# ecg_2017_nano.net
KiCad netlist of a schematic drawn in EAGLE
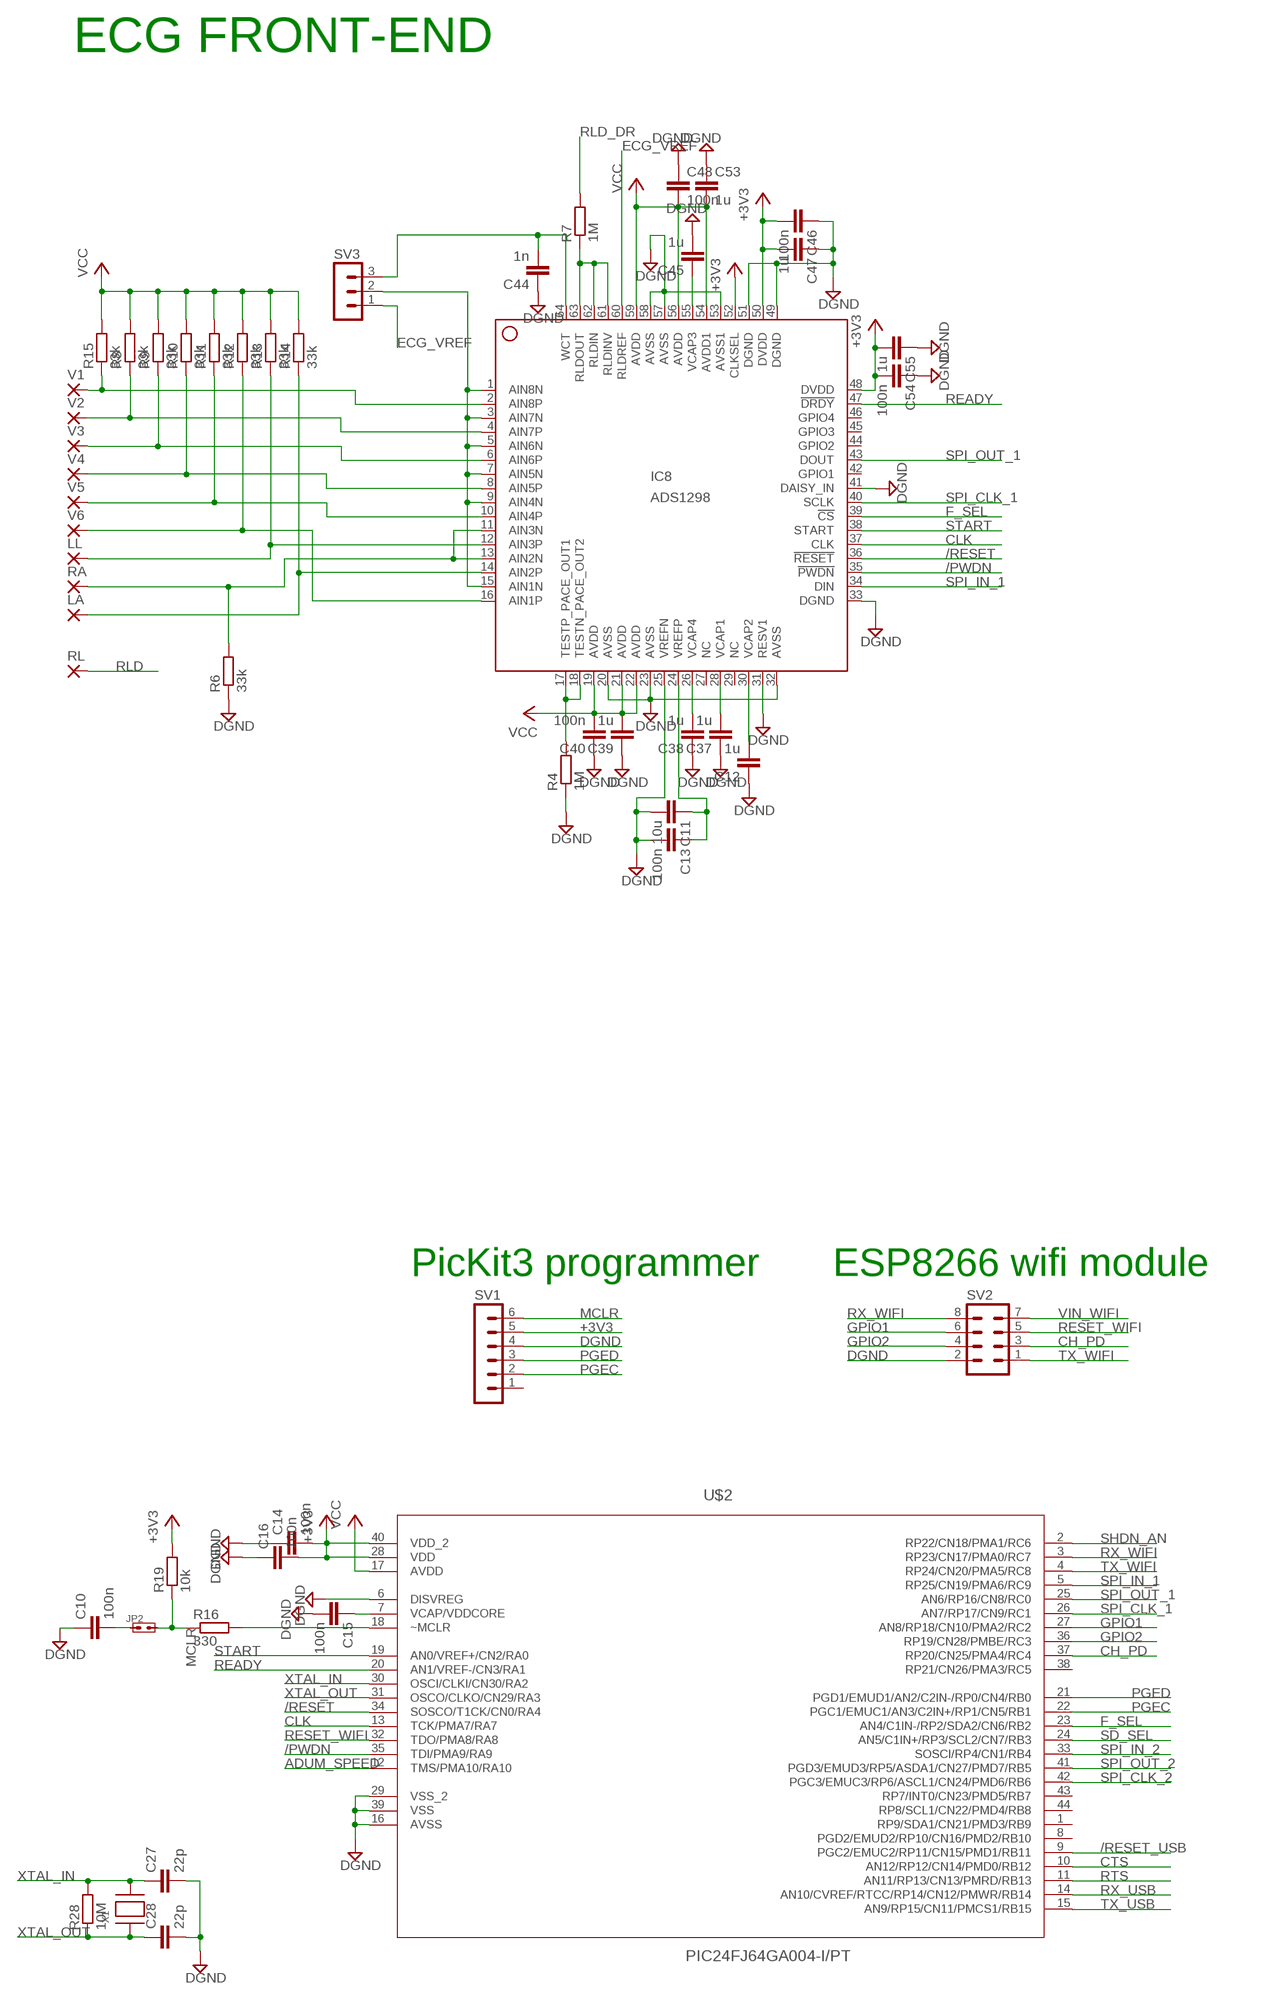
[diagram p0: schematic, sheet 1, part 1 of 2]
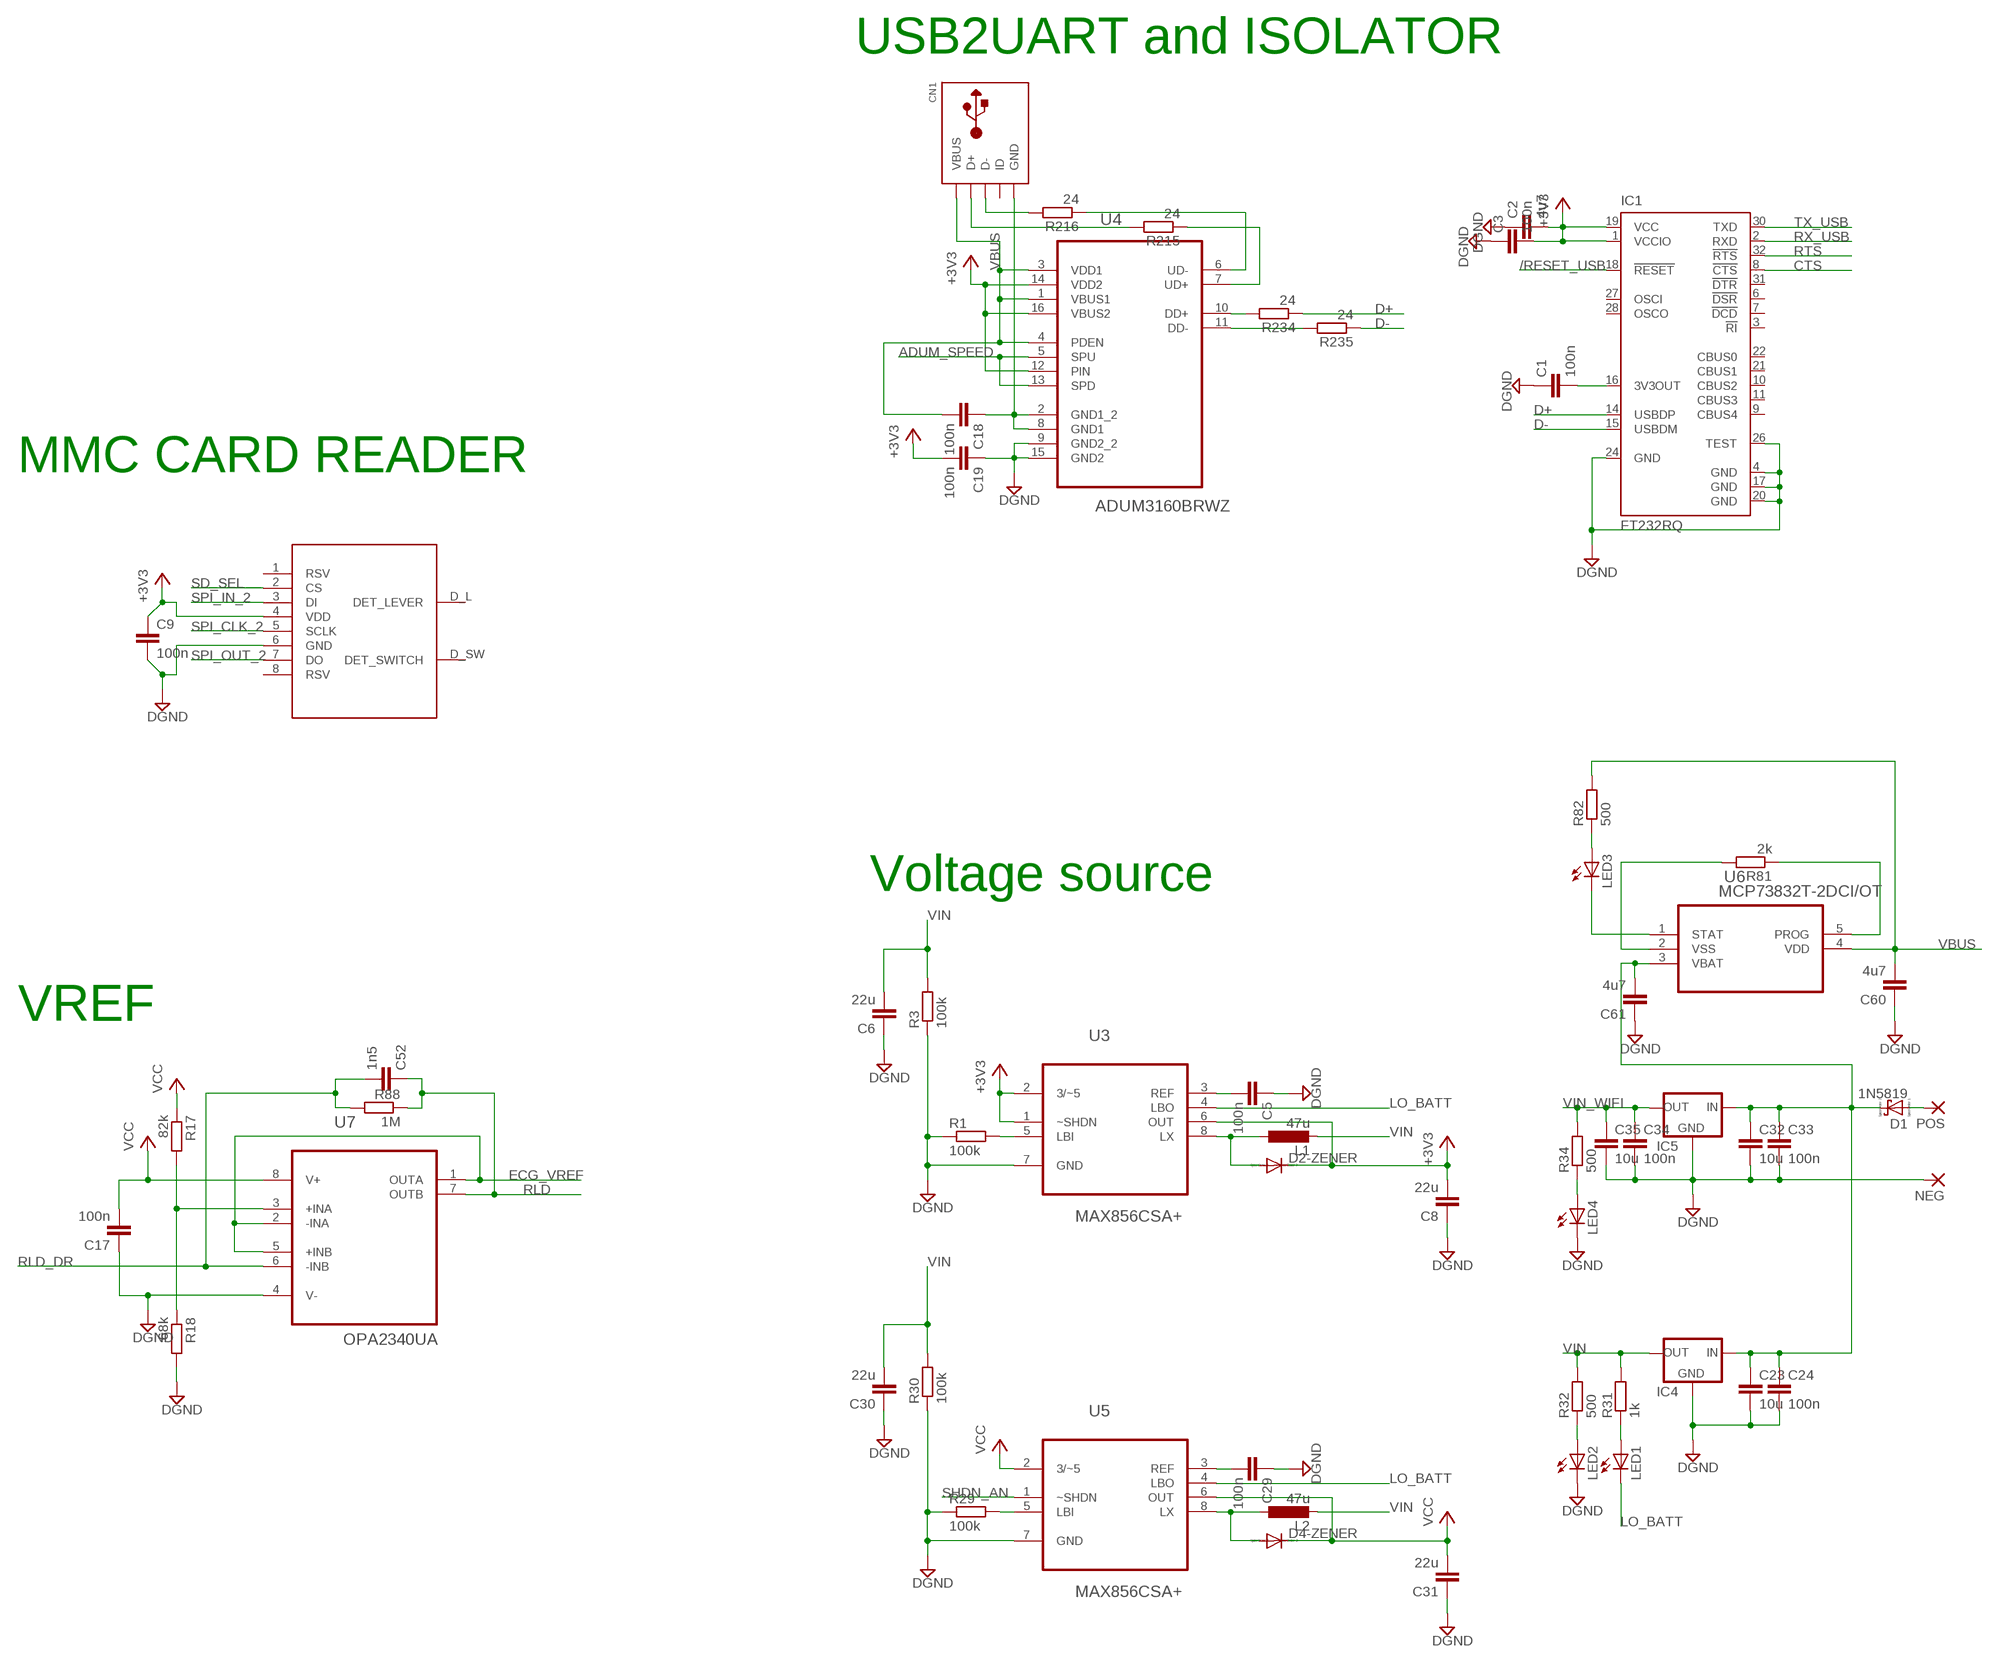
[diagram p1: schematic, sheet 1, part 2 of 2]

(export (version "E")
  (design (tool "Eeschema 10.0.6"))
  (components
    (comp (ref "C1")
      (value "100n")
      (footprint "eagle-import:C0603")
      (libsource (lib "eagle-import") (part "C-EUC0603"))
    )
    (comp (ref "C2")
      (value "4u7")
      (footprint "eagle-import:C0603")
      (libsource (lib "eagle-import") (part "C-EUC0603"))
    )
    (comp (ref "C3")
      (value "100n")
      (footprint "eagle-import:C0603")
      (libsource (lib "eagle-import") (part "C-EUC0603"))
    )
    (comp (ref "C5")
      (value "100n")
      (footprint "eagle-import:C0805")
      (libsource (lib "eagle-import") (part "C-EUC0805"))
    )
    (comp (ref "C6")
      (value "22u")
      (footprint "eagle-import:C0805")
      (libsource (lib "eagle-import") (part "C-EUC0805"))
    )
    (comp (ref "C8")
      (value "22u")
      (footprint "eagle-import:C0805")
      (libsource (lib "eagle-import") (part "C-EUC0805"))
    )
    (comp (ref "C9")
      (value "100n")
      (footprint "eagle-import:C0603")
      (libsource (lib "eagle-import") (part "C-EUC0603"))
    )
    (comp (ref "C10")
      (value "100n")
      (footprint "eagle-import:C0603")
      (libsource (lib "eagle-import") (part "C-EUC0603"))
    )
    (comp (ref "C11")
      (value "10u")
      (footprint "eagle-import:C0402")
      (libsource (lib "eagle-import") (part "C-EUC0402"))
    )
    (comp (ref "C12")
      (value "1u")
      (footprint "eagle-import:C0402")
      (libsource (lib "eagle-import") (part "C-EUC0402"))
    )
    (comp (ref "C13")
      (value "100n")
      (footprint "eagle-import:C0402")
      (libsource (lib "eagle-import") (part "C-EUC0402"))
    )
    (comp (ref "C14")
      (value "100n")
      (footprint "eagle-import:C0603")
      (libsource (lib "eagle-import") (part "C-EUC0603"))
    )
    (comp (ref "C15")
      (value "100n")
      (footprint "eagle-import:C0603")
      (libsource (lib "eagle-import") (part "C-EUC0603"))
    )
    (comp (ref "C16")
      (value "100n")
      (footprint "eagle-import:C0603")
      (libsource (lib "eagle-import") (part "C-EUC0603"))
    )
    (comp (ref "C17")
      (value "100n")
      (footprint "eagle-import:C0603")
      (libsource (lib "eagle-import") (part "C-EUC0603"))
    )
    (comp (ref "C18")
      (value "100n")
      (footprint "eagle-import:C0603")
      (libsource (lib "eagle-import") (part "C-EUC0603"))
    )
    (comp (ref "C19")
      (value "100n")
      (footprint "eagle-import:C0603")
      (libsource (lib "eagle-import") (part "C-EUC0603"))
    )
    (comp (ref "C23")
      (value "10u")
      (footprint "eagle-import:C0805")
      (libsource (lib "eagle-import") (part "C-EUC0805"))
    )
    (comp (ref "C24")
      (value "100n")
      (footprint "eagle-import:C0805")
      (libsource (lib "eagle-import") (part "C-EUC0805"))
    )
    (comp (ref "C27")
      (value "22p")
      (footprint "eagle-import:C0603")
      (libsource (lib "eagle-import") (part "C-EUC0603"))
    )
    (comp (ref "C28")
      (value "22p")
      (footprint "eagle-import:C0603")
      (libsource (lib "eagle-import") (part "C-EUC0603"))
    )
    (comp (ref "C29")
      (value "100n")
      (footprint "eagle-import:C0805")
      (libsource (lib "eagle-import") (part "C-EUC0805"))
    )
    (comp (ref "C30")
      (value "22u")
      (footprint "eagle-import:C0805")
      (libsource (lib "eagle-import") (part "C-EUC0805"))
    )
    (comp (ref "C31")
      (value "22u")
      (footprint "eagle-import:C0805")
      (libsource (lib "eagle-import") (part "C-EUC0805"))
    )
    (comp (ref "C32")
      (value "10u")
      (footprint "eagle-import:C0805")
      (libsource (lib "eagle-import") (part "C-EUC0805"))
    )
    (comp (ref "C33")
      (value "100n")
      (footprint "eagle-import:C0805")
      (libsource (lib "eagle-import") (part "C-EUC0805"))
    )
    (comp (ref "C34")
      (value "100n")
      (footprint "eagle-import:C0805")
      (libsource (lib "eagle-import") (part "C-EUC0805"))
    )
    (comp (ref "C35")
      (value "10u")
      (footprint "eagle-import:C0805")
      (libsource (lib "eagle-import") (part "C-EUC0805"))
    )
    (comp (ref "C37")
      (value "1u")
      (footprint "eagle-import:C0402")
      (libsource (lib "eagle-import") (part "C-EUC0402"))
    )
    (comp (ref "C38")
      (value "1u")
      (footprint "eagle-import:C0402")
      (libsource (lib "eagle-import") (part "C-EUC0402"))
    )
    (comp (ref "C39")
      (value "1u")
      (footprint "eagle-import:C0402")
      (libsource (lib "eagle-import") (part "C-EUC0402"))
    )
    (comp (ref "C40")
      (value "100n")
      (footprint "eagle-import:C0402")
      (libsource (lib "eagle-import") (part "C-EUC0402"))
    )
    (comp (ref "C44")
      (value "1n")
      (footprint "eagle-import:C0402")
      (libsource (lib "eagle-import") (part "C-EUC0402"))
    )
    (comp (ref "C45")
      (value "1u")
      (footprint "eagle-import:C0402")
      (libsource (lib "eagle-import") (part "C-EUC0402"))
    )
    (comp (ref "C46")
      (value "100n")
      (footprint "eagle-import:C0402")
      (libsource (lib "eagle-import") (part "C-EUC0402"))
    )
    (comp (ref "C47")
      (value "1u")
      (footprint "eagle-import:C0402")
      (libsource (lib "eagle-import") (part "C-EUC0402"))
    )
    (comp (ref "C48")
      (value "100n")
      (footprint "eagle-import:C0402")
      (libsource (lib "eagle-import") (part "C-EUC0402"))
    )
    (comp (ref "C52")
      (value "1n5")
      (footprint "eagle-import:C0603")
      (libsource (lib "eagle-import") (part "C-EUC0603"))
    )
    (comp (ref "C53")
      (value "1u")
      (footprint "eagle-import:C0402")
      (libsource (lib "eagle-import") (part "C-EUC0402"))
    )
    (comp (ref "C54")
      (value "100n")
      (footprint "eagle-import:C0402")
      (libsource (lib "eagle-import") (part "C-EUC0402"))
    )
    (comp (ref "C55")
      (value "1u")
      (footprint "eagle-import:C0402")
      (libsource (lib "eagle-import") (part "C-EUC0402"))
    )
    (comp (ref "C60")
      (value "4u7")
      (footprint "eagle-import:C0805")
      (libsource (lib "eagle-import") (part "C-EUC0805"))
    )
    (comp (ref "C61")
      (value "4u7")
      (footprint "eagle-import:C0805")
      (libsource (lib "eagle-import") (part "C-EUC0805"))
    )
    (comp (ref "CN1")
      (value "USBMINIB")
      (footprint "eagle-import:USB-MINIB")
      (libsource (lib "eagle-import") (part "USBMINIB"))
    )
    (comp (ref "D1")
      (value "1N5819")
      (footprint "eagle-import:DIODE_SMB")
      (libsource (lib "eagle-import") (part "SCHOTTKY-DIODE"))
    )
    (comp (ref "D2-ZENER")
      (value "DIODE-MICROMELF-R")
      (footprint "eagle-import:MICROMELF-R")
      (libsource (lib "eagle-import") (part "DIODE-MICROMELF-R"))
    )
    (comp (ref "D4-ZENER")
      (value "DIODE-MICROMELF-R")
      (footprint "eagle-import:MICROMELF-R")
      (libsource (lib "eagle-import") (part "DIODE-MICROMELF-R"))
    )
    (comp (ref "IC1")
      (value "FT232RQ")
      (footprint "eagle-import:QFN32")
      (libsource (lib "eagle-import") (part "FT232RQ"))
    )
    (comp (ref "IC4")
      (value "R-783.3-0.5")
      (footprint "eagle-import:R-78XX")
      (libsource (lib "eagle-import") (part "R-783.3-0.5"))
    )
    (comp (ref "IC5")
      (value "R-783.3-0.5")
      (footprint "eagle-import:R-78XX")
      (libsource (lib "eagle-import") (part "R-783.3-0.5"))
    )
    (comp (ref "IC8")
      (value "ADS1298")
      (footprint "eagle-import:HTQFP-64-PAP")
      (fields (field (name "MPN") "ADS1294IPAG"))
      (libsource (lib "eagle-import") (part "ADS1298"))
    )
    (comp (ref "JP2")
      (value "JMP2")
      (footprint "eagle-import:JP2")
      (libsource (lib "eagle-import") (part "JMP2"))
    )
    (comp (ref "L1")
      (value "47u")
      (footprint "eagle-import:L2012C")
      (libsource (lib "eagle-import") (part "L-EUL2012C"))
    )
    (comp (ref "L2")
      (value "47u")
      (footprint "eagle-import:L2012C")
      (libsource (lib "eagle-import") (part "L-EUL2012C"))
    )
    (comp (ref "LA")
      (value "2,54/1,0")
      (footprint "eagle-import:2,54_1,0")
      (libsource (lib "eagle-import") (part "2,54/1,0"))
    )
    (comp (ref "LED1")
      (value "LEDSML0805")
      (footprint "eagle-import:SML0805")
      (libsource (lib "eagle-import") (part "LEDSML0805"))
    )
    (comp (ref "LED2")
      (value "LEDSML0805")
      (footprint "eagle-import:SML0805")
      (libsource (lib "eagle-import") (part "LEDSML0805"))
    )
    (comp (ref "LED3")
      (value "LEDSML0805")
      (footprint "eagle-import:SML0805")
      (libsource (lib "eagle-import") (part "LEDSML0805"))
    )
    (comp (ref "LED4")
      (value "LEDSML0805")
      (footprint "eagle-import:SML0805")
      (libsource (lib "eagle-import") (part "LEDSML0805"))
    )
    (comp (ref "LL")
      (value "2,54/1,0")
      (footprint "eagle-import:2,54_1,0")
      (libsource (lib "eagle-import") (part "2,54/1,0"))
    )
    (comp (ref "NEG")
      (value "2,54/1,0")
      (footprint "eagle-import:2,54_1,0")
      (libsource (lib "eagle-import") (part "2,54/1,0"))
    )
    (comp (ref "POS")
      (value "2,54/1,0")
      (footprint "eagle-import:2,54_1,0")
      (libsource (lib "eagle-import") (part "2,54/1,0"))
    )
    (comp (ref "R1")
      (value "100k")
      (footprint "eagle-import:R0805")
      (libsource (lib "eagle-import") (part "R0805"))
    )
    (comp (ref "R3")
      (value "100k")
      (footprint "eagle-import:R0805")
      (libsource (lib "eagle-import") (part "R0805"))
    )
    (comp (ref "R4")
      (value "1M")
      (footprint "eagle-import:R0603")
      (libsource (lib "eagle-import") (part "R0603"))
    )
    (comp (ref "R6")
      (value "33k")
      (footprint "eagle-import:R0603")
      (libsource (lib "eagle-import") (part "R0603"))
    )
    (comp (ref "R7")
      (value "1M")
      (footprint "eagle-import:R0603")
      (libsource (lib "eagle-import") (part "R0603"))
    )
    (comp (ref "R8")
      (value "33k")
      (footprint "eagle-import:R0603")
      (libsource (lib "eagle-import") (part "R0603"))
    )
    (comp (ref "R9")
      (value "33k")
      (footprint "eagle-import:R0603")
      (libsource (lib "eagle-import") (part "R0603"))
    )
    (comp (ref "R10")
      (value "33k")
      (footprint "eagle-import:R0603")
      (libsource (lib "eagle-import") (part "R0603"))
    )
    (comp (ref "R11")
      (value "33k")
      (footprint "eagle-import:R0603")
      (libsource (lib "eagle-import") (part "R0603"))
    )
    (comp (ref "R12")
      (value "33k")
      (footprint "eagle-import:R0603")
      (libsource (lib "eagle-import") (part "R0603"))
    )
    (comp (ref "R13")
      (value "33k")
      (footprint "eagle-import:R0603")
      (libsource (lib "eagle-import") (part "R0603"))
    )
    (comp (ref "R14")
      (value "33k")
      (footprint "eagle-import:R0603")
      (libsource (lib "eagle-import") (part "R0603"))
    )
    (comp (ref "R15")
      (value "33k")
      (footprint "eagle-import:R0603")
      (libsource (lib "eagle-import") (part "R0603"))
    )
    (comp (ref "R16")
      (value "330")
      (footprint "eagle-import:R0603")
      (libsource (lib "eagle-import") (part "R0603"))
    )
    (comp (ref "R17")
      (value "82k")
      (footprint "eagle-import:R0603")
      (libsource (lib "eagle-import") (part "R0603"))
    )
    (comp (ref "R18")
      (value "68k")
      (footprint "eagle-import:R0603")
      (libsource (lib "eagle-import") (part "R0603"))
    )
    (comp (ref "R19")
      (value "10k")
      (footprint "eagle-import:R0603")
      (libsource (lib "eagle-import") (part "R0603"))
    )
    (comp (ref "R28")
      (value "10M")
      (footprint "eagle-import:R0603")
      (libsource (lib "eagle-import") (part "R-EU_R0603"))
    )
    (comp (ref "R29")
      (value "100k")
      (footprint "eagle-import:R0805")
      (libsource (lib "eagle-import") (part "R0805"))
    )
    (comp (ref "R30")
      (value "100k")
      (footprint "eagle-import:R0805")
      (libsource (lib "eagle-import") (part "R0805"))
    )
    (comp (ref "R31")
      (value "1k")
      (footprint "eagle-import:R0805")
      (libsource (lib "eagle-import") (part "R0805"))
    )
    (comp (ref "R32")
      (value "500")
      (footprint "eagle-import:R0805")
      (libsource (lib "eagle-import") (part "R0805"))
    )
    (comp (ref "R34")
      (value "500")
      (footprint "eagle-import:R0805")
      (libsource (lib "eagle-import") (part "R0805"))
    )
    (comp (ref "R81")
      (value "2k")
      (footprint "eagle-import:R0805")
      (libsource (lib "eagle-import") (part "R0805"))
    )
    (comp (ref "R82")
      (value "500")
      (footprint "eagle-import:R0805")
      (libsource (lib "eagle-import") (part "R0805"))
    )
    (comp (ref "R88")
      (value "1M")
      (footprint "eagle-import:R0603")
      (libsource (lib "eagle-import") (part "R0603"))
    )
    (comp (ref "R215")
      (value "24")
      (footprint "eagle-import:R0603")
      (libsource (lib "eagle-import") (part "R0603"))
    )
    (comp (ref "R216")
      (value "24")
      (footprint "eagle-import:R0603")
      (libsource (lib "eagle-import") (part "R0603"))
    )
    (comp (ref "R234")
      (value "24")
      (footprint "eagle-import:R0603")
      (libsource (lib "eagle-import") (part "R0603"))
    )
    (comp (ref "R235")
      (value "24")
      (footprint "eagle-import:R0603")
      (libsource (lib "eagle-import") (part "R0603"))
    )
    (comp (ref "RA")
      (value "2,54/1,0")
      (footprint "eagle-import:2,54_1,0")
      (libsource (lib "eagle-import") (part "2,54/1,0"))
    )
    (comp (ref "RL")
      (value "2,54/1,0")
      (footprint "eagle-import:2,54_1,0")
      (libsource (lib "eagle-import") (part "2,54/1,0"))
    )
    (comp (ref "SV1")
      (value "MA06-1")
      (footprint "eagle-import:MA06-1")
      (libsource (lib "eagle-import") (part "MA06-1"))
    )
    (comp (ref "SV2")
      (value "MA04-2")
      (footprint "eagle-import:MA04-2")
      (libsource (lib "eagle-import") (part "MA04-2"))
    )
    (comp (ref "SV3")
      (value "MA03-1")
      (footprint "eagle-import:MA03-1")
      (libsource (lib "eagle-import") (part "MA03-1"))
    )
    (comp (ref "U$1")
      (value "MICROSDCARD_CONNECTOR")
      (footprint "eagle-import:MICROSDCARD_CONNECTOR")
      (libsource (lib "eagle-import") (part "MICROSDCARD_CONNECTOR"))
    )
    (comp (ref "U$2")
      (value "PIC24FJ64GA004-I/PT")
      (footprint "eagle-import:QFP80P1200X1200X120-44N")
      (libsource (lib "eagle-import") (part "PIC24FJ64GA004-I/PT"))
    )
    (comp (ref "U3")
      (value "MAX856CSA+")
      (footprint "eagle-import:SOIC127P600X175-8N")
      (libsource (lib "eagle-import") (part "MAX856CSA+"))
    )
    (comp (ref "U4")
      (value "ADUM3160BRWZ")
      (footprint "eagle-import:SOIC127P1032X265-16N")
      (libsource (lib "eagle-import") (part "ADUM3160BRWZ"))
    )
    (comp (ref "U5")
      (value "MAX856CSA+")
      (footprint "eagle-import:SOIC127P600X175-8N")
      (libsource (lib "eagle-import") (part "MAX856CSA+"))
    )
    (comp (ref "U6")
      (value "MCP73832T-2DCI/OT")
      (footprint "eagle-import:SOT95P300X145-5N")
      (libsource (lib "eagle-import") (part "MCP73832T-2DCI/OT"))
    )
    (comp (ref "U7")
      (value "OPA2340UA")
      (footprint "eagle-import:SOIC127P600X175-8N")
      (libsource (lib "eagle-import") (part "OPA2340UA"))
    )
    (comp (ref "V1")
      (value "2,54/1,0")
      (footprint "eagle-import:2,54_1,0")
      (libsource (lib "eagle-import") (part "2,54/1,0"))
    )
    (comp (ref "V2")
      (value "2,54/1,0")
      (footprint "eagle-import:2,54_1,0")
      (libsource (lib "eagle-import") (part "2,54/1,0"))
    )
    (comp (ref "V3")
      (value "2,54/1,0")
      (footprint "eagle-import:2,54_1,0")
      (libsource (lib "eagle-import") (part "2,54/1,0"))
    )
    (comp (ref "V4")
      (value "2,54/1,0")
      (footprint "eagle-import:2,54_1,0")
      (libsource (lib "eagle-import") (part "2,54/1,0"))
    )
    (comp (ref "V5")
      (value "2,54/1,0")
      (footprint "eagle-import:2,54_1,0")
      (libsource (lib "eagle-import") (part "2,54/1,0"))
    )
    (comp (ref "V6")
      (value "2,54/1,0")
      (footprint "eagle-import:2,54_1,0")
      (libsource (lib "eagle-import") (part "2,54/1,0"))
    )
    (comp (ref "X1")
      (value "XTAL-3.2X1.5")
      (footprint "eagle-import:XTAL3215")
      (libsource (lib "eagle-import") (part "XTAL-3.2X1.5"))
    )
  )
  (nets
    (net (code "1") (name "+3V3") (class "Default")
      (node (ref "C14") (pin "2") (pinfunction "2_2") (pintype "passive"))
      (node (ref "C16") (pin "2") (pinfunction "2_2") (pintype "passive"))
      (node (ref "C19") (pin "2") (pinfunction "2_2") (pintype "passive"))
      (node (ref "C2") (pin "2") (pinfunction "2_2") (pintype "passive"))
      (node (ref "C3") (pin "2") (pinfunction "2_2") (pintype "passive"))
      (node (ref "C46") (pin "2") (pinfunction "2_2") (pintype "passive"))
      (node (ref "C47") (pin "2") (pinfunction "2_2") (pintype "passive"))
      (node (ref "C54") (pin "2") (pinfunction "2_2") (pintype "passive"))
      (node (ref "C55") (pin "2") (pinfunction "2_2") (pintype "passive"))
      (node (ref "C8") (pin "2") (pinfunction "2_2") (pintype "passive"))
      (node (ref "C9") (pin "1") (pinfunction "1_1") (pintype "passive"))
      (node (ref "D2-ZENER") (pin "C") (pinfunction "C_C") (pintype "passive"))
      (node (ref "IC1") (pin "1") (pinfunction "VCCIO_1") (pintype "power_in"))
      (node (ref "IC1") (pin "19") (pinfunction "VCC_19") (pintype "power_in"))
      (node (ref "IC8") (pin "48") (pinfunction "DVDD_48") (pintype "power_in"))
      (node (ref "IC8") (pin "50") (pinfunction "DVDD_50") (pintype "power_in"))
      (node (ref "IC8") (pin "52") (pinfunction "CLKSEL_52") (pintype "input"))
      (node (ref "R19") (pin "2") (pinfunction "2_2") (pintype "passive"))
      (node (ref "SV1") (pin "5") (pinfunction "5_5") (pintype "passive"))
      (node (ref "U$1") (pin "4") (pinfunction "VDD_4") (pintype "power_in"))
      (node (ref "U$2") (pin "28") (pinfunction "VDD_28") (pintype "power_in"))
      (node (ref "U$2") (pin "40") (pinfunction "VDD_2_40") (pintype "power_in"))
      (node (ref "U3") (pin "1") (pinfunction "~{SHDN}_1") (pintype "input"))
      (node (ref "U3") (pin "2") (pinfunction "3/~{5}_2") (pintype "input"))
      (node (ref "U3") (pin "6") (pinfunction "OUT_6") (pintype "output"))
      (node (ref "U4") (pin "12") (pinfunction "PIN_12") (pintype "input"))
      (node (ref "U4") (pin "14") (pinfunction "VDD2_14") (pintype "power_in"))
      (node (ref "U4") (pin "16") (pinfunction "VBUS2_16") (pintype "power_in"))
    )
    (net (code "2") (name "/ADUM_SPEED") (class "Default")
      (node (ref "U$2") (pin "12") (pinfunction "TMS/PMA10/RA10_12") (pintype "bidirectional"))
      (node (ref "U4") (pin "13") (pinfunction "SPD_13") (pintype "input"))
      (node (ref "U4") (pin "5") (pinfunction "SPU_5") (pintype "input"))
    )
    (net (code "3") (name "/CH_PD") (class "Default")
      (node (ref "SV2") (pin "3") (pinfunction "3_3") (pintype "passive"))
      (node (ref "U$2") (pin "37") (pinfunction "RP20/CN25/PMA4/RC4_37") (pintype "bidirectional"))
    )
    (net (code "4") (name "/CLK") (class "Default")
      (node (ref "IC8") (pin "37") (pinfunction "CLK_37") (pintype "input"))
      (node (ref "U$2") (pin "13") (pinfunction "TCK/PMA7/RA7_13") (pintype "bidirectional"))
    )
    (net (code "5") (name "/CTS") (class "Default")
      (node (ref "IC1") (pin "8") (pinfunction "~{CTS}_8") (pintype "input"))
      (node (ref "U$2") (pin "10") (pinfunction "AN12/RP12/CN14/PMD0/RB12_10") (pintype "bidirectional"))
    )
    (net (code "6") (name "/D+") (class "Default")
      (node (ref "IC1") (pin "14") (pinfunction "USBDP_14") (pintype "bidirectional"))
      (node (ref "R234") (pin "1") (pinfunction "1_1") (pintype "passive"))
    )
    (net (code "7") (name "/D-") (class "Default")
      (node (ref "IC1") (pin "15") (pinfunction "USBDM_15") (pintype "bidirectional"))
      (node (ref "R235") (pin "1") (pinfunction "1_1") (pintype "passive"))
    )
    (net (code "8") (name "/ECG_VREF") (class "Default")
      (node (ref "IC8") (pin "60") (pinfunction "RLDREF_60") (pintype "input"))
      (node (ref "SV3") (pin "1") (pinfunction "1_1") (pintype "passive"))
      (node (ref "U7") (pin "1") (pinfunction "OUTA_1") (pintype "output"))
      (node (ref "U7") (pin "2") (pinfunction "-INA_2") (pintype "input"))
      (node (ref "U7") (pin "5") (pinfunction "+INB_5") (pintype "input"))
    )
    (net (code "9") (name "/F_SEL") (class "Default")
      (node (ref "IC8") (pin "39") (pinfunction "~{CS}_39") (pintype "input"))
      (node (ref "U$2") (pin "23") (pinfunction "AN4/C1IN-/RP2/SDA2/CN6/RB2_23") (pintype "bidirectional"))
    )
    (net (code "10") (name "/GPIO1") (class "Default")
      (node (ref "SV2") (pin "6") (pinfunction "6_6") (pintype "passive"))
      (node (ref "U$2") (pin "27") (pinfunction "AN8/RP18/CN10/PMA2/RC2_27") (pintype "bidirectional"))
    )
    (net (code "11") (name "/GPIO2") (class "Default")
      (node (ref "SV2") (pin "4") (pinfunction "4_4") (pintype "passive"))
      (node (ref "U$2") (pin "36") (pinfunction "RP19/CN28/PMBE/RC3_36") (pintype "bidirectional"))
    )
    (net (code "12") (name "/LO_BATT") (class "Default")
      (node (ref "LED1") (pin "C") (pinfunction "C_C") (pintype "passive"))
      (node (ref "U3") (pin "4") (pinfunction "LBO_4") (pintype "output"))
      (node (ref "U5") (pin "4") (pinfunction "LBO_4") (pintype "output"))
    )
    (net (code "13") (name "/MCLR") (class "Default")
      (node (ref "JP2") (pin "2") (pinfunction "P$2_2") (pintype "bidirectional"))
      (node (ref "R16") (pin "1") (pinfunction "1_1") (pintype "passive"))
      (node (ref "R19") (pin "1") (pinfunction "1_1") (pintype "passive"))
      (node (ref "SV1") (pin "6") (pinfunction "6_6") (pintype "passive"))
    )
    (net (code "14") (name "/PGEC") (class "Default")
      (node (ref "SV1") (pin "2") (pinfunction "2_2") (pintype "passive"))
      (node (ref "U$2") (pin "22") (pinfunction "PGC1/EMUC1/AN3/C2IN+/RP1/CN5/RB1_22") (pintype "bidirectional"))
    )
    (net (code "15") (name "/PGED") (class "Default")
      (node (ref "SV1") (pin "3") (pinfunction "3_3") (pintype "passive"))
      (node (ref "U$2") (pin "21") (pinfunction "PGD1/EMUD1/AN2/C2IN-/RP0/CN4/RB0_21") (pintype "bidirectional"))
    )
    (net (code "16") (name "/READY") (class "Default")
      (node (ref "IC8") (pin "47") (pinfunction "~{DRDY}_47") (pintype "input"))
      (node (ref "U$2") (pin "20") (pinfunction "AN1/VREF-/CN3/RA1_20") (pintype "bidirectional"))
    )
    (net (code "17") (name "/RESET_WIFI") (class "Default")
      (node (ref "SV2") (pin "5") (pinfunction "5_5") (pintype "passive"))
      (node (ref "U$2") (pin "32") (pinfunction "TDO/PMA8/RA8_32") (pintype "bidirectional"))
    )
    (net (code "18") (name "/RLD") (class "Default")
      (node (ref "C52") (pin "1") (pinfunction "1_1") (pintype "passive"))
      (node (ref "R88") (pin "1") (pinfunction "1_1") (pintype "passive"))
      (node (ref "RL") (pin "1") (pinfunction "P_1") (pintype "passive"))
      (node (ref "U7") (pin "7") (pinfunction "OUTB_7") (pintype "output"))
    )
    (net (code "19") (name "/RLD_DR") (class "Default")
      (node (ref "C52") (pin "2") (pinfunction "2_2") (pintype "passive"))
      (node (ref "R7") (pin "2") (pinfunction "2_2") (pintype "passive"))
      (node (ref "R88") (pin "2") (pinfunction "2_2") (pintype "passive"))
      (node (ref "U7") (pin "6") (pinfunction "-INB_6") (pintype "input"))
    )
    (net (code "20") (name "/RTS") (class "Default")
      (node (ref "IC1") (pin "32") (pinfunction "~{RTS}_32") (pintype "output"))
      (node (ref "U$2") (pin "11") (pinfunction "AN11/RP13/CN13/PMRD/RB13_11") (pintype "bidirectional"))
    )
    (net (code "21") (name "/RX_USB") (class "Default")
      (node (ref "IC1") (pin "2") (pinfunction "RXD_2") (pintype "input"))
      (node (ref "U$2") (pin "14") (pinfunction "AN10/CVREF/RTCC/RP14/CN12/PMWR/RB14_14") (pintype "bidirectional"))
    )
    (net (code "22") (name "/RX_WIFI") (class "Default")
      (node (ref "SV2") (pin "8") (pinfunction "8_8") (pintype "passive"))
      (node (ref "U$2") (pin "3") (pinfunction "RP23/CN17/PMA0/RC7_3") (pintype "bidirectional"))
    )
    (net (code "23") (name "/SD_SEL") (class "Default")
      (node (ref "U$1") (pin "2") (pinfunction "CS_2") (pintype "input"))
      (node (ref "U$2") (pin "24") (pinfunction "AN5/C1IN+/RP3/SCL2/CN7/RB3_24") (pintype "bidirectional"))
    )
    (net (code "24") (name "/SHDN_AN") (class "Default")
      (node (ref "U$2") (pin "2") (pinfunction "RP22/CN18/PMA1/RC6_2") (pintype "bidirectional"))
      (node (ref "U5") (pin "1") (pinfunction "~{SHDN}_1") (pintype "input"))
    )
    (net (code "25") (name "/SPI_CLK_1") (class "Default")
      (node (ref "IC8") (pin "40") (pinfunction "SCLK_40") (pintype "bidirectional"))
      (node (ref "U$2") (pin "26") (pinfunction "AN7/RP17/CN9/RC1_26") (pintype "bidirectional"))
    )
    (net (code "26") (name "/SPI_CLK_2") (class "Default")
      (node (ref "U$1") (pin "5") (pinfunction "SCLK_5") (pintype "input"))
      (node (ref "U$2") (pin "42") (pinfunction "PGC3/EMUC3/RP6/ASCL1/CN24/PMD6/RB6_42") (pintype "bidirectional"))
    )
    (net (code "27") (name "/SPI_IN_1") (class "Default")
      (node (ref "IC8") (pin "34") (pinfunction "DIN_34") (pintype "input"))
      (node (ref "U$2") (pin "5") (pinfunction "RP25/CN19/PMA6/RC9_5") (pintype "bidirectional"))
    )
    (net (code "28") (name "/SPI_IN_2") (class "Default")
      (node (ref "U$1") (pin "3") (pinfunction "DI_3") (pintype "input"))
      (node (ref "U$2") (pin "33") (pinfunction "SOSCI/RP4/CN1/RB4_33") (pintype "bidirectional"))
    )
    (net (code "29") (name "/SPI_OUT_1") (class "Default")
      (node (ref "IC8") (pin "43") (pinfunction "DOUT_43") (pintype "bidirectional"))
      (node (ref "U$2") (pin "25") (pinfunction "AN6/RP16/CN8/RC0_25") (pintype "bidirectional"))
    )
    (net (code "30") (name "/SPI_OUT_2") (class "Default")
      (node (ref "U$1") (pin "7") (pinfunction "DO_7") (pintype "output"))
      (node (ref "U$2") (pin "41") (pinfunction "PGD3/EMUD3/RP5/ASDA1/CN27/PMD7/RB5_41") (pintype "bidirectional"))
    )
    (net (code "31") (name "/START") (class "Default")
      (node (ref "IC8") (pin "38") (pinfunction "START_38") (pintype "input"))
      (node (ref "U$2") (pin "19") (pinfunction "AN0/VREF+/CN2/RA0_19") (pintype "bidirectional"))
    )
    (net (code "32") (name "/TX_USB") (class "Default")
      (node (ref "IC1") (pin "30") (pinfunction "TXD_30") (pintype "output"))
      (node (ref "U$2") (pin "15") (pinfunction "AN9/RP15/CN11/PMCS1/RB15_15") (pintype "bidirectional"))
    )
    (net (code "33") (name "/TX_WIFI") (class "Default")
      (node (ref "SV2") (pin "1") (pinfunction "1_1") (pintype "passive"))
      (node (ref "U$2") (pin "4") (pinfunction "RP24/CN20/PMA5/RC8_4") (pintype "bidirectional"))
    )
    (net (code "34") (name "/VBUS") (class "Default")
      (node (ref "C18") (pin "2") (pinfunction "2_2") (pintype "passive"))
      (node (ref "C60") (pin "2") (pinfunction "2_2") (pintype "passive"))
      (node (ref "CN1") (pin "VBUS") (pinfunction "VBUS_VBUS") (pintype "power_in"))
      (node (ref "R82") (pin "2") (pinfunction "2_2") (pintype "passive"))
      (node (ref "U4") (pin "1") (pinfunction "VBUS1_1") (pintype "power_in"))
      (node (ref "U4") (pin "3") (pinfunction "VDD1_3") (pintype "power_in"))
      (node (ref "U4") (pin "4") (pinfunction "PDEN_4") (pintype "input"))
      (node (ref "U6") (pin "4") (pinfunction "VDD_4") (pintype "power_in"))
    )
    (net (code "35") (name "/VIN") (class "Default")
      (node (ref "C30") (pin "2") (pinfunction "2_2") (pintype "passive"))
      (node (ref "C6") (pin "2") (pinfunction "2_2") (pintype "passive"))
      (node (ref "IC4") (pin "OUT") (pinfunction "OUT_OUT") (pintype "passive"))
      (node (ref "L1") (pin "2") (pinfunction "2_2") (pintype "passive"))
      (node (ref "L2") (pin "2") (pinfunction "2_2") (pintype "passive"))
      (node (ref "R3") (pin "2") (pinfunction "2_2") (pintype "passive"))
      (node (ref "R30") (pin "2") (pinfunction "2_2") (pintype "passive"))
      (node (ref "R31") (pin "2") (pinfunction "2_2") (pintype "passive"))
      (node (ref "R32") (pin "2") (pinfunction "2_2") (pintype "passive"))
    )
    (net (code "36") (name "/VIN_WIFI") (class "Default")
      (node (ref "C34") (pin "1") (pinfunction "1_1") (pintype "passive"))
      (node (ref "C35") (pin "1") (pinfunction "1_1") (pintype "passive"))
      (node (ref "IC5") (pin "OUT") (pinfunction "OUT_OUT") (pintype "passive"))
      (node (ref "R34") (pin "2") (pinfunction "2_2") (pintype "passive"))
      (node (ref "SV2") (pin "7") (pinfunction "7_7") (pintype "passive"))
    )
    (net (code "37") (name "/XTAL_IN") (class "Default")
      (node (ref "C27") (pin "1") (pinfunction "1_1") (pintype "passive"))
      (node (ref "R28") (pin "2") (pinfunction "2_2") (pintype "passive"))
      (node (ref "U$2") (pin "30") (pinfunction "OSCI/CLKI/CN30/RA2_30") (pintype "bidirectional"))
      (node (ref "X1") (pin "P$2") (pinfunction "P$2_P$2") (pintype "bidirectional"))
    )
    (net (code "38") (name "/XTAL_OUT") (class "Default")
      (node (ref "C28") (pin "1") (pinfunction "1_1") (pintype "passive"))
      (node (ref "R28") (pin "1") (pinfunction "1_1") (pintype "passive"))
      (node (ref "U$2") (pin "31") (pinfunction "OSCO/CLKO/CN29/RA3_31") (pintype "bidirectional"))
      (node (ref "X1") (pin "P$1") (pinfunction "P$1_P$1") (pintype "bidirectional"))
    )
    (net (code "39") (name "/{slash}PWDN") (class "Default")
      (node (ref "IC8") (pin "35") (pinfunction "~{PWDN}_35") (pintype "input"))
      (node (ref "U$2") (pin "35") (pinfunction "TDI/PMA9/RA9_35") (pintype "bidirectional"))
    )
    (net (code "40") (name "/{slash}RESET") (class "Default")
      (node (ref "IC8") (pin "36") (pinfunction "~{RESET}_36") (pintype "input"))
      (node (ref "U$2") (pin "34") (pinfunction "SOSCO/T1CK/CN0/RA4_34") (pintype "bidirectional"))
    )
    (net (code "41") (name "/{slash}RESET_USB") (class "Default")
      (node (ref "IC1") (pin "18") (pinfunction "~{RESET}_18") (pintype "input"))
      (node (ref "U$2") (pin "9") (pinfunction "PGC2/EMUC2/RP11/CN15/PMD1/RB11_9") (pintype "bidirectional"))
    )
    (net (code "42") (name "DGND") (class "Default")
      (node (ref "C1") (pin "1") (pinfunction "1_1") (pintype "passive"))
      (node (ref "C10") (pin "1") (pinfunction "1_1") (pintype "passive"))
      (node (ref "C11") (pin "2") (pinfunction "2_2") (pintype "passive"))
      (node (ref "C12") (pin "1") (pinfunction "1_1") (pintype "passive"))
      (node (ref "C13") (pin "2") (pinfunction "2_2") (pintype "passive"))
      (node (ref "C14") (pin "1") (pinfunction "1_1") (pintype "passive"))
      (node (ref "C15") (pin "2") (pinfunction "2_2") (pintype "passive"))
      (node (ref "C16") (pin "1") (pinfunction "1_1") (pintype "passive"))
      (node (ref "C17") (pin "1") (pinfunction "1_1") (pintype "passive"))
      (node (ref "C19") (pin "1") (pinfunction "1_1") (pintype "passive"))
      (node (ref "C2") (pin "1") (pinfunction "1_1") (pintype "passive"))
      (node (ref "C23") (pin "2") (pinfunction "2_2") (pintype "passive"))
      (node (ref "C24") (pin "2") (pinfunction "2_2") (pintype "passive"))
      (node (ref "C27") (pin "2") (pinfunction "2_2") (pintype "passive"))
      (node (ref "C28") (pin "2") (pinfunction "2_2") (pintype "passive"))
      (node (ref "C29") (pin "1") (pinfunction "1_1") (pintype "passive"))
      (node (ref "C3") (pin "1") (pinfunction "1_1") (pintype "passive"))
      (node (ref "C30") (pin "1") (pinfunction "1_1") (pintype "passive"))
      (node (ref "C31") (pin "1") (pinfunction "1_1") (pintype "passive"))
      (node (ref "C32") (pin "2") (pinfunction "2_2") (pintype "passive"))
      (node (ref "C33") (pin "2") (pinfunction "2_2") (pintype "passive"))
      (node (ref "C34") (pin "2") (pinfunction "2_2") (pintype "passive"))
      (node (ref "C35") (pin "2") (pinfunction "2_2") (pintype "passive"))
      (node (ref "C37") (pin "1") (pinfunction "1_1") (pintype "passive"))
      (node (ref "C38") (pin "1") (pinfunction "1_1") (pintype "passive"))
      (node (ref "C39") (pin "1") (pinfunction "1_1") (pintype "passive"))
      (node (ref "C40") (pin "1") (pinfunction "1_1") (pintype "passive"))
      (node (ref "C44") (pin "1") (pinfunction "1_1") (pintype "passive"))
      (node (ref "C45") (pin "2") (pinfunction "2_2") (pintype "passive"))
      (node (ref "C46") (pin "1") (pinfunction "1_1") (pintype "passive"))
      (node (ref "C47") (pin "1") (pinfunction "1_1") (pintype "passive"))
      (node (ref "C48") (pin "1") (pinfunction "1_1") (pintype "passive"))
      (node (ref "C5") (pin "1") (pinfunction "1_1") (pintype "passive"))
      (node (ref "C53") (pin "1") (pinfunction "1_1") (pintype "passive"))
      (node (ref "C54") (pin "1") (pinfunction "1_1") (pintype "passive"))
      (node (ref "C55") (pin "1") (pinfunction "1_1") (pintype "passive"))
      (node (ref "C6") (pin "1") (pinfunction "1_1") (pintype "passive"))
      (node (ref "C60") (pin "1") (pinfunction "1_1") (pintype "passive"))
      (node (ref "C61") (pin "1") (pinfunction "1_1") (pintype "passive"))
      (node (ref "C8") (pin "1") (pinfunction "1_1") (pintype "passive"))
      (node (ref "C9") (pin "2") (pinfunction "2_2") (pintype "passive"))
      (node (ref "IC1") (pin "17") (pinfunction "GND_17") (pintype "power_in"))
      (node (ref "IC1") (pin "20") (pinfunction "GND_20") (pintype "power_in"))
      (node (ref "IC1") (pin "24") (pinfunction "GND_24") (pintype "power_in"))
      (node (ref "IC1") (pin "26") (pinfunction "TEST_26") (pintype "input"))
      (node (ref "IC1") (pin "4") (pinfunction "GND_4") (pintype "power_in"))
      (node (ref "IC4") (pin "GND") (pinfunction "GND_GND") (pintype "input"))
      (node (ref "IC5") (pin "GND") (pinfunction "GND_GND") (pintype "input"))
      (node (ref "IC8") (pin "20") (pinfunction "AVSS_20") (pintype "power_in"))
      (node (ref "IC8") (pin "23") (pinfunction "AVSS_23") (pintype "power_in"))
      (node (ref "IC8") (pin "25") (pinfunction "VREFN_25") (pintype "input"))
      (node (ref "IC8") (pin "31") (pinfunction "RESV1_31") (pintype "input"))
      (node (ref "IC8") (pin "32") (pinfunction "AVSS_32") (pintype "power_in"))
      (node (ref "IC8") (pin "33") (pinfunction "DGND_33") (pintype "power_in"))
      (node (ref "IC8") (pin "41") (pinfunction "DAISY_IN_41") (pintype "input"))
      (node (ref "IC8") (pin "49") (pinfunction "DGND_49") (pintype "power_in"))
      (node (ref "IC8") (pin "51") (pinfunction "DGND_51") (pintype "power_in"))
      (node (ref "IC8") (pin "53") (pinfunction "AVSS1_53") (pintype "power_in"))
      (node (ref "IC8") (pin "57") (pinfunction "AVSS_57") (pintype "power_in"))
      (node (ref "IC8") (pin "58") (pinfunction "AVSS_58") (pintype "power_in"))
      (node (ref "LED2") (pin "C") (pinfunction "C_C") (pintype "passive"))
      (node (ref "LED4") (pin "C") (pinfunction "C_C") (pintype "passive"))
      (node (ref "NEG") (pin "1") (pinfunction "P_1") (pintype "passive"))
      (node (ref "R1") (pin "1") (pinfunction "1_1") (pintype "passive"))
      (node (ref "R18") (pin "2") (pinfunction "2_2") (pintype "passive"))
      (node (ref "R29") (pin "1") (pinfunction "1_1") (pintype "passive"))
      (node (ref "R3") (pin "1") (pinfunction "1_1") (pintype "passive"))
      (node (ref "R30") (pin "1") (pinfunction "1_1") (pintype "passive"))
      (node (ref "R4") (pin "1") (pinfunction "1_1") (pintype "passive"))
      (node (ref "R6") (pin "1") (pinfunction "1_1") (pintype "passive"))
      (node (ref "SV1") (pin "4") (pinfunction "4_4") (pintype "passive"))
      (node (ref "SV2") (pin "2") (pinfunction "2_2") (pintype "passive"))
      (node (ref "U$1") (pin "6") (pinfunction "GND_6") (pintype "power_in"))
      (node (ref "U$2") (pin "16") (pinfunction "AVSS_16") (pintype "power_in"))
      (node (ref "U$2") (pin "29") (pinfunction "VSS_2_29") (pintype "power_in"))
      (node (ref "U$2") (pin "39") (pinfunction "VSS_39") (pintype "power_in"))
      (node (ref "U$2") (pin "6") (pinfunction "DISVREG_6") (pintype "passive"))
      (node (ref "U3") (pin "7") (pinfunction "GND_7") (pintype "passive"))
      (node (ref "U4") (pin "15") (pinfunction "GND2_15") (pintype "passive"))
      (node (ref "U4") (pin "9") (pinfunction "GND2_2_9") (pintype "passive"))
      (node (ref "U5") (pin "7") (pinfunction "GND_7") (pintype "passive"))
      (node (ref "U7") (pin "4") (pinfunction "V-_4") (pintype "power_in"))
    )
    (net (code "43") (name "Net-(CN1-PadD+)") (class "Default")
      (node (ref "CN1") (pin "D+") (pinfunction "D+_D+") (pintype "bidirectional"))
      (node (ref "R215") (pin "2") (pinfunction "2_2") (pintype "passive"))
    )
    (net (code "44") (name "Net-(CN1-PadD-)") (class "Default")
      (node (ref "CN1") (pin "D-") (pinfunction "D-_D-") (pintype "bidirectional"))
      (node (ref "R216") (pin "2") (pinfunction "2_2") (pintype "passive"))
    )
    (net (code "45") (name "Net-(D1-A)") (class "Default")
      (node (ref "C23") (pin "1") (pinfunction "1_1") (pintype "passive"))
      (node (ref "C24") (pin "1") (pinfunction "1_1") (pintype "passive"))
      (node (ref "C32") (pin "1") (pinfunction "1_1") (pintype "passive"))
      (node (ref "C33") (pin "1") (pinfunction "1_1") (pintype "passive"))
      (node (ref "C61") (pin "2") (pinfunction "2_2") (pintype "passive"))
      (node (ref "D1") (pin "C") (pinfunction "A_C") (pintype "passive"))
      (node (ref "IC4") (pin "IN") (pinfunction "IN_IN") (pintype "input"))
      (node (ref "IC5") (pin "IN") (pinfunction "IN_IN") (pintype "input"))
      (node (ref "U6") (pin "3") (pinfunction "VBAT_3") (pintype "input"))
    )
    (net (code "46") (name "Net-(D1-C)") (class "Default")
      (node (ref "D1") (pin "A") (pinfunction "C_A") (pintype "passive"))
      (node (ref "POS") (pin "1") (pinfunction "P_1") (pintype "passive"))
    )
    (net (code "47") (name "Net-(IC1-3V3OUT)") (class "Default")
      (node (ref "C1") (pin "2") (pinfunction "2_2") (pintype "passive"))
      (node (ref "IC1") (pin "16") (pinfunction "3V3OUT_16") (pintype "output"))
    )
    (net (code "48") (name "Net-(IC8-AIN1N)") (class "Default")
      (node (ref "IC8") (pin "1") (pinfunction "AIN8N_1") (pintype "input"))
      (node (ref "IC8") (pin "15") (pinfunction "AIN1N_15") (pintype "input"))
      (node (ref "IC8") (pin "3") (pinfunction "AIN7N_3") (pintype "input"))
      (node (ref "IC8") (pin "5") (pinfunction "AIN6N_5") (pintype "input"))
      (node (ref "IC8") (pin "7") (pinfunction "AIN5N_7") (pintype "input"))
      (node (ref "IC8") (pin "9") (pinfunction "AIN4N_9") (pintype "input"))
      (node (ref "SV3") (pin "2") (pinfunction "2_2") (pintype "passive"))
    )
    (net (code "49") (name "Net-(IC8-AIN1P)") (class "Default")
      (node (ref "IC8") (pin "16") (pinfunction "AIN1P_16") (pintype "input"))
      (node (ref "R12") (pin "1") (pinfunction "1_1") (pintype "passive"))
      (node (ref "V6") (pin "1") (pinfunction "P_1") (pintype "passive"))
    )
    (net (code "50") (name "Net-(IC8-AIN2N)") (class "Default")
      (node (ref "IC8") (pin "11") (pinfunction "AIN3N_11") (pintype "input"))
      (node (ref "IC8") (pin "13") (pinfunction "AIN2N_13") (pintype "input"))
      (node (ref "R6") (pin "2") (pinfunction "2_2") (pintype "passive"))
      (node (ref "RA") (pin "1") (pinfunction "P_1") (pintype "passive"))
    )
    (net (code "51") (name "Net-(IC8-AIN2P)") (class "Default")
      (node (ref "IC8") (pin "14") (pinfunction "AIN2P_14") (pintype "input"))
      (node (ref "LA") (pin "1") (pinfunction "P_1") (pintype "passive"))
      (node (ref "R14") (pin "1") (pinfunction "1_1") (pintype "passive"))
    )
    (net (code "52") (name "Net-(IC8-AIN3P)") (class "Default")
      (node (ref "IC8") (pin "12") (pinfunction "AIN3P_12") (pintype "input"))
      (node (ref "LL") (pin "1") (pinfunction "P_1") (pintype "passive"))
      (node (ref "R13") (pin "1") (pinfunction "1_1") (pintype "passive"))
    )
    (net (code "53") (name "Net-(IC8-AIN4P)") (class "Default")
      (node (ref "IC8") (pin "10") (pinfunction "AIN4P_10") (pintype "input"))
      (node (ref "R11") (pin "1") (pinfunction "1_1") (pintype "passive"))
      (node (ref "V5") (pin "1") (pinfunction "P_1") (pintype "passive"))
    )
    (net (code "54") (name "Net-(IC8-AIN5P)") (class "Default")
      (node (ref "IC8") (pin "8") (pinfunction "AIN5P_8") (pintype "input"))
      (node (ref "R10") (pin "1") (pinfunction "1_1") (pintype "passive"))
      (node (ref "V4") (pin "1") (pinfunction "P_1") (pintype "passive"))
    )
    (net (code "55") (name "Net-(IC8-AIN6P)") (class "Default")
      (node (ref "IC8") (pin "6") (pinfunction "AIN6P_6") (pintype "input"))
      (node (ref "R9") (pin "1") (pinfunction "1_1") (pintype "passive"))
      (node (ref "V3") (pin "1") (pinfunction "P_1") (pintype "passive"))
    )
    (net (code "56") (name "Net-(IC8-AIN7P)") (class "Default")
      (node (ref "IC8") (pin "4") (pinfunction "AIN7P_4") (pintype "input"))
      (node (ref "R8") (pin "1") (pinfunction "1_1") (pintype "passive"))
      (node (ref "V2") (pin "1") (pinfunction "P_1") (pintype "passive"))
    )
    (net (code "57") (name "Net-(IC8-AIN8P)") (class "Default")
      (node (ref "IC8") (pin "2") (pinfunction "AIN8P_2") (pintype "input"))
      (node (ref "R15") (pin "1") (pinfunction "1_1") (pintype "passive"))
      (node (ref "V1") (pin "1") (pinfunction "P_1") (pintype "passive"))
    )
    (net (code "58") (name "Net-(IC8-RLDIN)") (class "Default")
      (node (ref "IC8") (pin "61") (pinfunction "RLDINV_61") (pintype "bidirectional"))
      (node (ref "IC8") (pin "62") (pinfunction "RLDIN_62") (pintype "input"))
      (node (ref "IC8") (pin "63") (pinfunction "RLDOUT_63") (pintype "output"))
      (node (ref "R7") (pin "1") (pinfunction "1_1") (pintype "passive"))
    )
    (net (code "59") (name "Net-(IC8-TESTN_PACE_OUT2)") (class "Default")
      (node (ref "IC8") (pin "17") (pinfunction "TESTP_PACE_OUT1_17") (pintype "bidirectional"))
      (node (ref "IC8") (pin "18") (pinfunction "TESTN_PACE_OUT2_18") (pintype "bidirectional"))
      (node (ref "R4") (pin "2") (pinfunction "2_2") (pintype "passive"))
    )
    (net (code "60") (name "Net-(IC8-VCAP1)") (class "Default")
      (node (ref "C37") (pin "2") (pinfunction "2_2") (pintype "passive"))
      (node (ref "IC8") (pin "28") (pinfunction "VCAP1_28") (pintype "passive"))
    )
    (net (code "61") (name "Net-(IC8-VCAP2)") (class "Default")
      (node (ref "C12") (pin "2") (pinfunction "2_2") (pintype "passive"))
      (node (ref "IC8") (pin "30") (pinfunction "VCAP2_30") (pintype "passive"))
    )
    (net (code "62") (name "Net-(IC8-VCAP3)") (class "Default")
      (node (ref "C45") (pin "1") (pinfunction "1_1") (pintype "passive"))
      (node (ref "IC8") (pin "55") (pinfunction "VCAP3_55") (pintype "passive"))
    )
    (net (code "63") (name "Net-(IC8-VCAP4)") (class "Default")
      (node (ref "C38") (pin "2") (pinfunction "2_2") (pintype "passive"))
      (node (ref "IC8") (pin "26") (pinfunction "VCAP4_26") (pintype "passive"))
    )
    (net (code "64") (name "Net-(IC8-VREFP)") (class "Default")
      (node (ref "C11") (pin "1") (pinfunction "1_1") (pintype "passive"))
      (node (ref "C13") (pin "1") (pinfunction "1_1") (pintype "passive"))
      (node (ref "IC8") (pin "24") (pinfunction "VREFP_24") (pintype "input"))
    )
    (net (code "65") (name "Net-(IC8-WCT)") (class "Default")
      (node (ref "C44") (pin "2") (pinfunction "2_2") (pintype "passive"))
      (node (ref "IC8") (pin "64") (pinfunction "WCT_64") (pintype "output"))
      (node (ref "SV3") (pin "3") (pinfunction "3_3") (pintype "passive"))
    )
    (net (code "66") (name "Net-(JP2-P$1)") (class "Default")
      (node (ref "C10") (pin "2") (pinfunction "2_2") (pintype "passive"))
      (node (ref "JP2") (pin "1") (pinfunction "P$1_1") (pintype "bidirectional"))
    )
    (net (code "67") (name "Net-(LED1-PadA)") (class "Default")
      (node (ref "LED1") (pin "A") (pinfunction "A_A") (pintype "passive"))
      (node (ref "R31") (pin "1") (pinfunction "1_1") (pintype "passive"))
    )
    (net (code "68") (name "Net-(LED2-PadA)") (class "Default")
      (node (ref "LED2") (pin "A") (pinfunction "A_A") (pintype "passive"))
      (node (ref "R32") (pin "1") (pinfunction "1_1") (pintype "passive"))
    )
    (net (code "69") (name "Net-(LED3-PadA)") (class "Default")
      (node (ref "LED3") (pin "A") (pinfunction "A_A") (pintype "passive"))
      (node (ref "R82") (pin "1") (pinfunction "1_1") (pintype "passive"))
    )
    (net (code "70") (name "Net-(LED4-PadA)") (class "Default")
      (node (ref "LED4") (pin "A") (pinfunction "A_A") (pintype "passive"))
      (node (ref "R34") (pin "1") (pinfunction "1_1") (pintype "passive"))
    )
    (net (code "71") (name "Net-(U$2-VCAP{slash}VDDCORE)") (class "Default")
      (node (ref "C15") (pin "1") (pinfunction "1_1") (pintype "passive"))
      (node (ref "U$2") (pin "7") (pinfunction "VCAP/VDDCORE_7") (pintype "power_in"))
    )
    (net (code "72") (name "Net-(U$2-~{MCLR})") (class "Default")
      (node (ref "R16") (pin "2") (pinfunction "2_2") (pintype "passive"))
      (node (ref "U$2") (pin "18") (pinfunction "~{MCLR}_18") (pintype "bidirectional"))
    )
    (net (code "73") (name "Net-(U3-LBI)") (class "Default")
      (node (ref "R1") (pin "2") (pinfunction "2_2") (pintype "passive"))
      (node (ref "U3") (pin "5") (pinfunction "LBI_5") (pintype "input"))
    )
    (net (code "74") (name "Net-(U3-LX)") (class "Default")
      (node (ref "D2-ZENER") (pin "A") (pinfunction "A_A") (pintype "passive"))
      (node (ref "L1") (pin "1") (pinfunction "1_1") (pintype "passive"))
      (node (ref "U3") (pin "8") (pinfunction "LX_8") (pintype "output"))
    )
    (net (code "75") (name "Net-(U3-REF)") (class "Default")
      (node (ref "C5") (pin "2") (pinfunction "2_2") (pintype "passive"))
      (node (ref "U3") (pin "3") (pinfunction "REF_3") (pintype "output"))
    )
    (net (code "76") (name "Net-(U4-DD+)") (class "Default")
      (node (ref "R234") (pin "2") (pinfunction "2_2") (pintype "passive"))
      (node (ref "U4") (pin "10") (pinfunction "DD+_10") (pintype "bidirectional"))
    )
    (net (code "77") (name "Net-(U4-DD-)") (class "Default")
      (node (ref "R235") (pin "2") (pinfunction "2_2") (pintype "passive"))
      (node (ref "U4") (pin "11") (pinfunction "DD-_11") (pintype "bidirectional"))
    )
    (net (code "78") (name "Net-(U4-GND1)") (class "Default")
      (node (ref "C18") (pin "1") (pinfunction "1_1") (pintype "passive"))
      (node (ref "CN1") (pin "GND") (pinfunction "GND_GND") (pintype "power_in"))
      (node (ref "U4") (pin "2") (pinfunction "GND1_2_2") (pintype "passive"))
      (node (ref "U4") (pin "8") (pinfunction "GND1_8") (pintype "passive"))
    )
    (net (code "79") (name "Net-(U4-UD+)") (class "Default")
      (node (ref "R215") (pin "1") (pinfunction "1_1") (pintype "passive"))
      (node (ref "U4") (pin "7") (pinfunction "UD+_7") (pintype "bidirectional"))
    )
    (net (code "80") (name "Net-(U4-UD-)") (class "Default")
      (node (ref "R216") (pin "1") (pinfunction "1_1") (pintype "passive"))
      (node (ref "U4") (pin "6") (pinfunction "UD-_6") (pintype "bidirectional"))
    )
    (net (code "81") (name "Net-(U5-LBI)") (class "Default")
      (node (ref "R29") (pin "2") (pinfunction "2_2") (pintype "passive"))
      (node (ref "U5") (pin "5") (pinfunction "LBI_5") (pintype "input"))
    )
    (net (code "82") (name "Net-(U5-LX)") (class "Default")
      (node (ref "D4-ZENER") (pin "A") (pinfunction "A_A") (pintype "passive"))
      (node (ref "L2") (pin "1") (pinfunction "1_1") (pintype "passive"))
      (node (ref "U5") (pin "8") (pinfunction "LX_8") (pintype "output"))
    )
    (net (code "83") (name "Net-(U5-REF)") (class "Default")
      (node (ref "C29") (pin "2") (pinfunction "2_2") (pintype "passive"))
      (node (ref "U5") (pin "3") (pinfunction "REF_3") (pintype "output"))
    )
    (net (code "84") (name "Net-(U6-PROG)") (class "Default")
      (node (ref "R81") (pin "1") (pinfunction "1_1") (pintype "passive"))
      (node (ref "U6") (pin "5") (pinfunction "PROG_5") (pintype "input"))
    )
    (net (code "85") (name "Net-(U6-STAT)") (class "Default")
      (node (ref "LED3") (pin "C") (pinfunction "C_C") (pintype "passive"))
      (node (ref "U6") (pin "1") (pinfunction "STAT_1") (pintype "input"))
    )
    (net (code "86") (name "Net-(U6-VSS)") (class "Default")
      (node (ref "R81") (pin "2") (pinfunction "2_2") (pintype "passive"))
      (node (ref "U6") (pin "2") (pinfunction "VSS_2") (pintype "passive"))
    )
    (net (code "87") (name "Net-(U7-+INA)") (class "Default")
      (node (ref "R17") (pin "2") (pinfunction "2_2") (pintype "passive"))
      (node (ref "R18") (pin "1") (pinfunction "1_1") (pintype "passive"))
      (node (ref "U7") (pin "3") (pinfunction "+INA_3") (pintype "input"))
    )
    (net (code "88") (name "VCC") (class "Default")
      (node (ref "C17") (pin "2") (pinfunction "2_2") (pintype "passive"))
      (node (ref "C31") (pin "2") (pinfunction "2_2") (pintype "passive"))
      (node (ref "C39") (pin "2") (pinfunction "2_2") (pintype "passive"))
      (node (ref "C40") (pin "2") (pinfunction "2_2") (pintype "passive"))
      (node (ref "C48") (pin "2") (pinfunction "2_2") (pintype "passive"))
      (node (ref "C53") (pin "2") (pinfunction "2_2") (pintype "passive"))
      (node (ref "D4-ZENER") (pin "C") (pinfunction "C_C") (pintype "passive"))
      (node (ref "IC8") (pin "19") (pinfunction "AVDD_19") (pintype "power_in"))
      (node (ref "IC8") (pin "21") (pinfunction "AVDD_21") (pintype "power_in"))
      (node (ref "IC8") (pin "22") (pinfunction "AVDD_22") (pintype "power_in"))
      (node (ref "IC8") (pin "54") (pinfunction "AVDD1_54") (pintype "power_in"))
      (node (ref "IC8") (pin "56") (pinfunction "AVDD_56") (pintype "power_in"))
      (node (ref "IC8") (pin "59") (pinfunction "AVDD_59") (pintype "power_in"))
      (node (ref "R10") (pin "2") (pinfunction "2_2") (pintype "passive"))
      (node (ref "R11") (pin "2") (pinfunction "2_2") (pintype "passive"))
      (node (ref "R12") (pin "2") (pinfunction "2_2") (pintype "passive"))
      (node (ref "R13") (pin "2") (pinfunction "2_2") (pintype "passive"))
      (node (ref "R14") (pin "2") (pinfunction "2_2") (pintype "passive"))
      (node (ref "R15") (pin "2") (pinfunction "2_2") (pintype "passive"))
      (node (ref "R17") (pin "1") (pinfunction "1_1") (pintype "passive"))
      (node (ref "R8") (pin "2") (pinfunction "2_2") (pintype "passive"))
      (node (ref "R9") (pin "2") (pinfunction "2_2") (pintype "passive"))
      (node (ref "U$2") (pin "17") (pinfunction "AVDD_17") (pintype "power_in"))
      (node (ref "U5") (pin "2") (pinfunction "3/~{5}_2") (pintype "input"))
      (node (ref "U5") (pin "6") (pinfunction "OUT_6") (pintype "output"))
      (node (ref "U7") (pin "8") (pinfunction "V+_8") (pintype "power_in"))
    )
    (net (code "89") (name "unconnected-(CN1-PadID)") (class "Default")
      (node (ref "CN1") (pin "ID") (pinfunction "ID_ID") (pintype "bidirectional"))
    )
    (net (code "90") (name "unconnected-(IC1-CBUS0-Pad22)") (class "Default")
      (node (ref "IC1") (pin "22") (pinfunction "CBUS0_22") (pintype "bidirectional"))
    )
    (net (code "91") (name "unconnected-(IC1-CBUS1-Pad21)") (class "Default")
      (node (ref "IC1") (pin "21") (pinfunction "CBUS1_21") (pintype "bidirectional"))
    )
    (net (code "92") (name "unconnected-(IC1-CBUS2-Pad10)") (class "Default")
      (node (ref "IC1") (pin "10") (pinfunction "CBUS2_10") (pintype "bidirectional"))
    )
    (net (code "93") (name "unconnected-(IC1-CBUS3-Pad11)") (class "Default")
      (node (ref "IC1") (pin "11") (pinfunction "CBUS3_11") (pintype "bidirectional"))
    )
    (net (code "94") (name "unconnected-(IC1-CBUS4-Pad9)") (class "Default")
      (node (ref "IC1") (pin "9") (pinfunction "CBUS4_9") (pintype "bidirectional"))
    )
    (net (code "95") (name "unconnected-(IC1-OSCI-Pad27)") (class "Default")
      (node (ref "IC1") (pin "27") (pinfunction "OSCI_27") (pintype "input"))
    )
    (net (code "96") (name "unconnected-(IC1-OSCO-Pad28)") (class "Default")
      (node (ref "IC1") (pin "28") (pinfunction "OSCO_28") (pintype "output"))
    )
    (net (code "97") (name "unconnected-(IC1-~{DCD}-Pad7)") (class "Default")
      (node (ref "IC1") (pin "7") (pinfunction "~{DCD}_7") (pintype "input"))
    )
    (net (code "98") (name "unconnected-(IC1-~{DSR}-Pad6)") (class "Default")
      (node (ref "IC1") (pin "6") (pinfunction "~{DSR}_6") (pintype "input"))
    )
    (net (code "99") (name "unconnected-(IC1-~{DTR}-Pad31)") (class "Default")
      (node (ref "IC1") (pin "31") (pinfunction "~{DTR}_31") (pintype "output"))
    )
    (net (code "100") (name "unconnected-(IC1-~{RI}-Pad3)") (class "Default")
      (node (ref "IC1") (pin "3") (pinfunction "~{RI}_3") (pintype "input"))
    )
    (net (code "101") (name "unconnected-(IC8-GPIO1-Pad42)") (class "Default")
      (node (ref "IC8") (pin "42") (pinfunction "GPIO1_42") (pintype "bidirectional"))
    )
    (net (code "102") (name "unconnected-(IC8-GPIO2-Pad44)") (class "Default")
      (node (ref "IC8") (pin "44") (pinfunction "GPIO2_44") (pintype "bidirectional"))
    )
    (net (code "103") (name "unconnected-(IC8-GPIO3-Pad45)") (class "Default")
      (node (ref "IC8") (pin "45") (pinfunction "GPIO3_45") (pintype "bidirectional"))
    )
    (net (code "104") (name "unconnected-(IC8-GPIO4-Pad46)") (class "Default")
      (node (ref "IC8") (pin "46") (pinfunction "GPIO4_46") (pintype "bidirectional"))
    )
    (net (code "105") (name "unconnected-(IC8-NC-Pad27)") (class "Default")
      (node (ref "IC8") (pin "27") (pinfunction "NC_27") (pintype "no_connect"))
    )
    (net (code "106") (name "unconnected-(IC8-NC-Pad29)") (class "Default")
      (node (ref "IC8") (pin "29") (pinfunction "NC_29") (pintype "no_connect"))
    )
    (net (code "107") (name "unconnected-(SV1-Pad1)") (class "Default")
      (node (ref "SV1") (pin "1") (pinfunction "1_1") (pintype "passive"))
    )
    (net (code "108") (name "unconnected-(U$1-DET_LEVER-PadD_L)") (class "Default")
      (node (ref "U$1") (pin "D_L") (pinfunction "DET_LEVER_D_L") (pintype "bidirectional"))
    )
    (net (code "109") (name "unconnected-(U$1-DET_SWITCH-PadD_SW)") (class "Default")
      (node (ref "U$1") (pin "D_SW") (pinfunction "DET_SWITCH_D_SW") (pintype "bidirectional"))
    )
    (net (code "110") (name "unconnected-(U$1-RSV-Pad1)") (class "Default")
      (node (ref "U$1") (pin "1") (pinfunction "RSV_1") (pintype "bidirectional"))
    )
    (net (code "111") (name "unconnected-(U$1-RSV-Pad8)") (class "Default")
      (node (ref "U$1") (pin "8") (pinfunction "RSV_8") (pintype "bidirectional"))
    )
    (net (code "112") (name "unconnected-(U$2-PGD2{slash}EMUD2{slash}RP10{slash}CN16{slash}PMD2{slash}RB10-Pad8)") (class "Default")
      (node (ref "U$2") (pin "8") (pinfunction "PGD2/EMUD2/RP10/CN16/PMD2/RB10_8") (pintype "bidirectional"))
    )
    (net (code "113") (name "unconnected-(U$2-RP7{slash}INT0{slash}CN23{slash}PMD5{slash}RB7-Pad43)") (class "Default")
      (node (ref "U$2") (pin "43") (pinfunction "RP7/INT0/CN23/PMD5/RB7_43") (pintype "bidirectional"))
    )
    (net (code "114") (name "unconnected-(U$2-RP8{slash}SCL1{slash}CN22{slash}PMD4{slash}RB8-Pad44)") (class "Default")
      (node (ref "U$2") (pin "44") (pinfunction "RP8/SCL1/CN22/PMD4/RB8_44") (pintype "bidirectional"))
    )
    (net (code "115") (name "unconnected-(U$2-RP9{slash}SDA1{slash}CN21{slash}PMD3{slash}RB9-Pad1)") (class "Default")
      (node (ref "U$2") (pin "1") (pinfunction "RP9/SDA1/CN21/PMD3/RB9_1") (pintype "bidirectional"))
    )
    (net (code "116") (name "unconnected-(U$2-RP21{slash}CN26{slash}PMA3{slash}RC5-Pad38)") (class "Default")
      (node (ref "U$2") (pin "38") (pinfunction "RP21/CN26/PMA3/RC5_38") (pintype "bidirectional"))
    )
  )
)
